# design.net
KiCad netlist of a schematic drawn in EasyEDA Pro
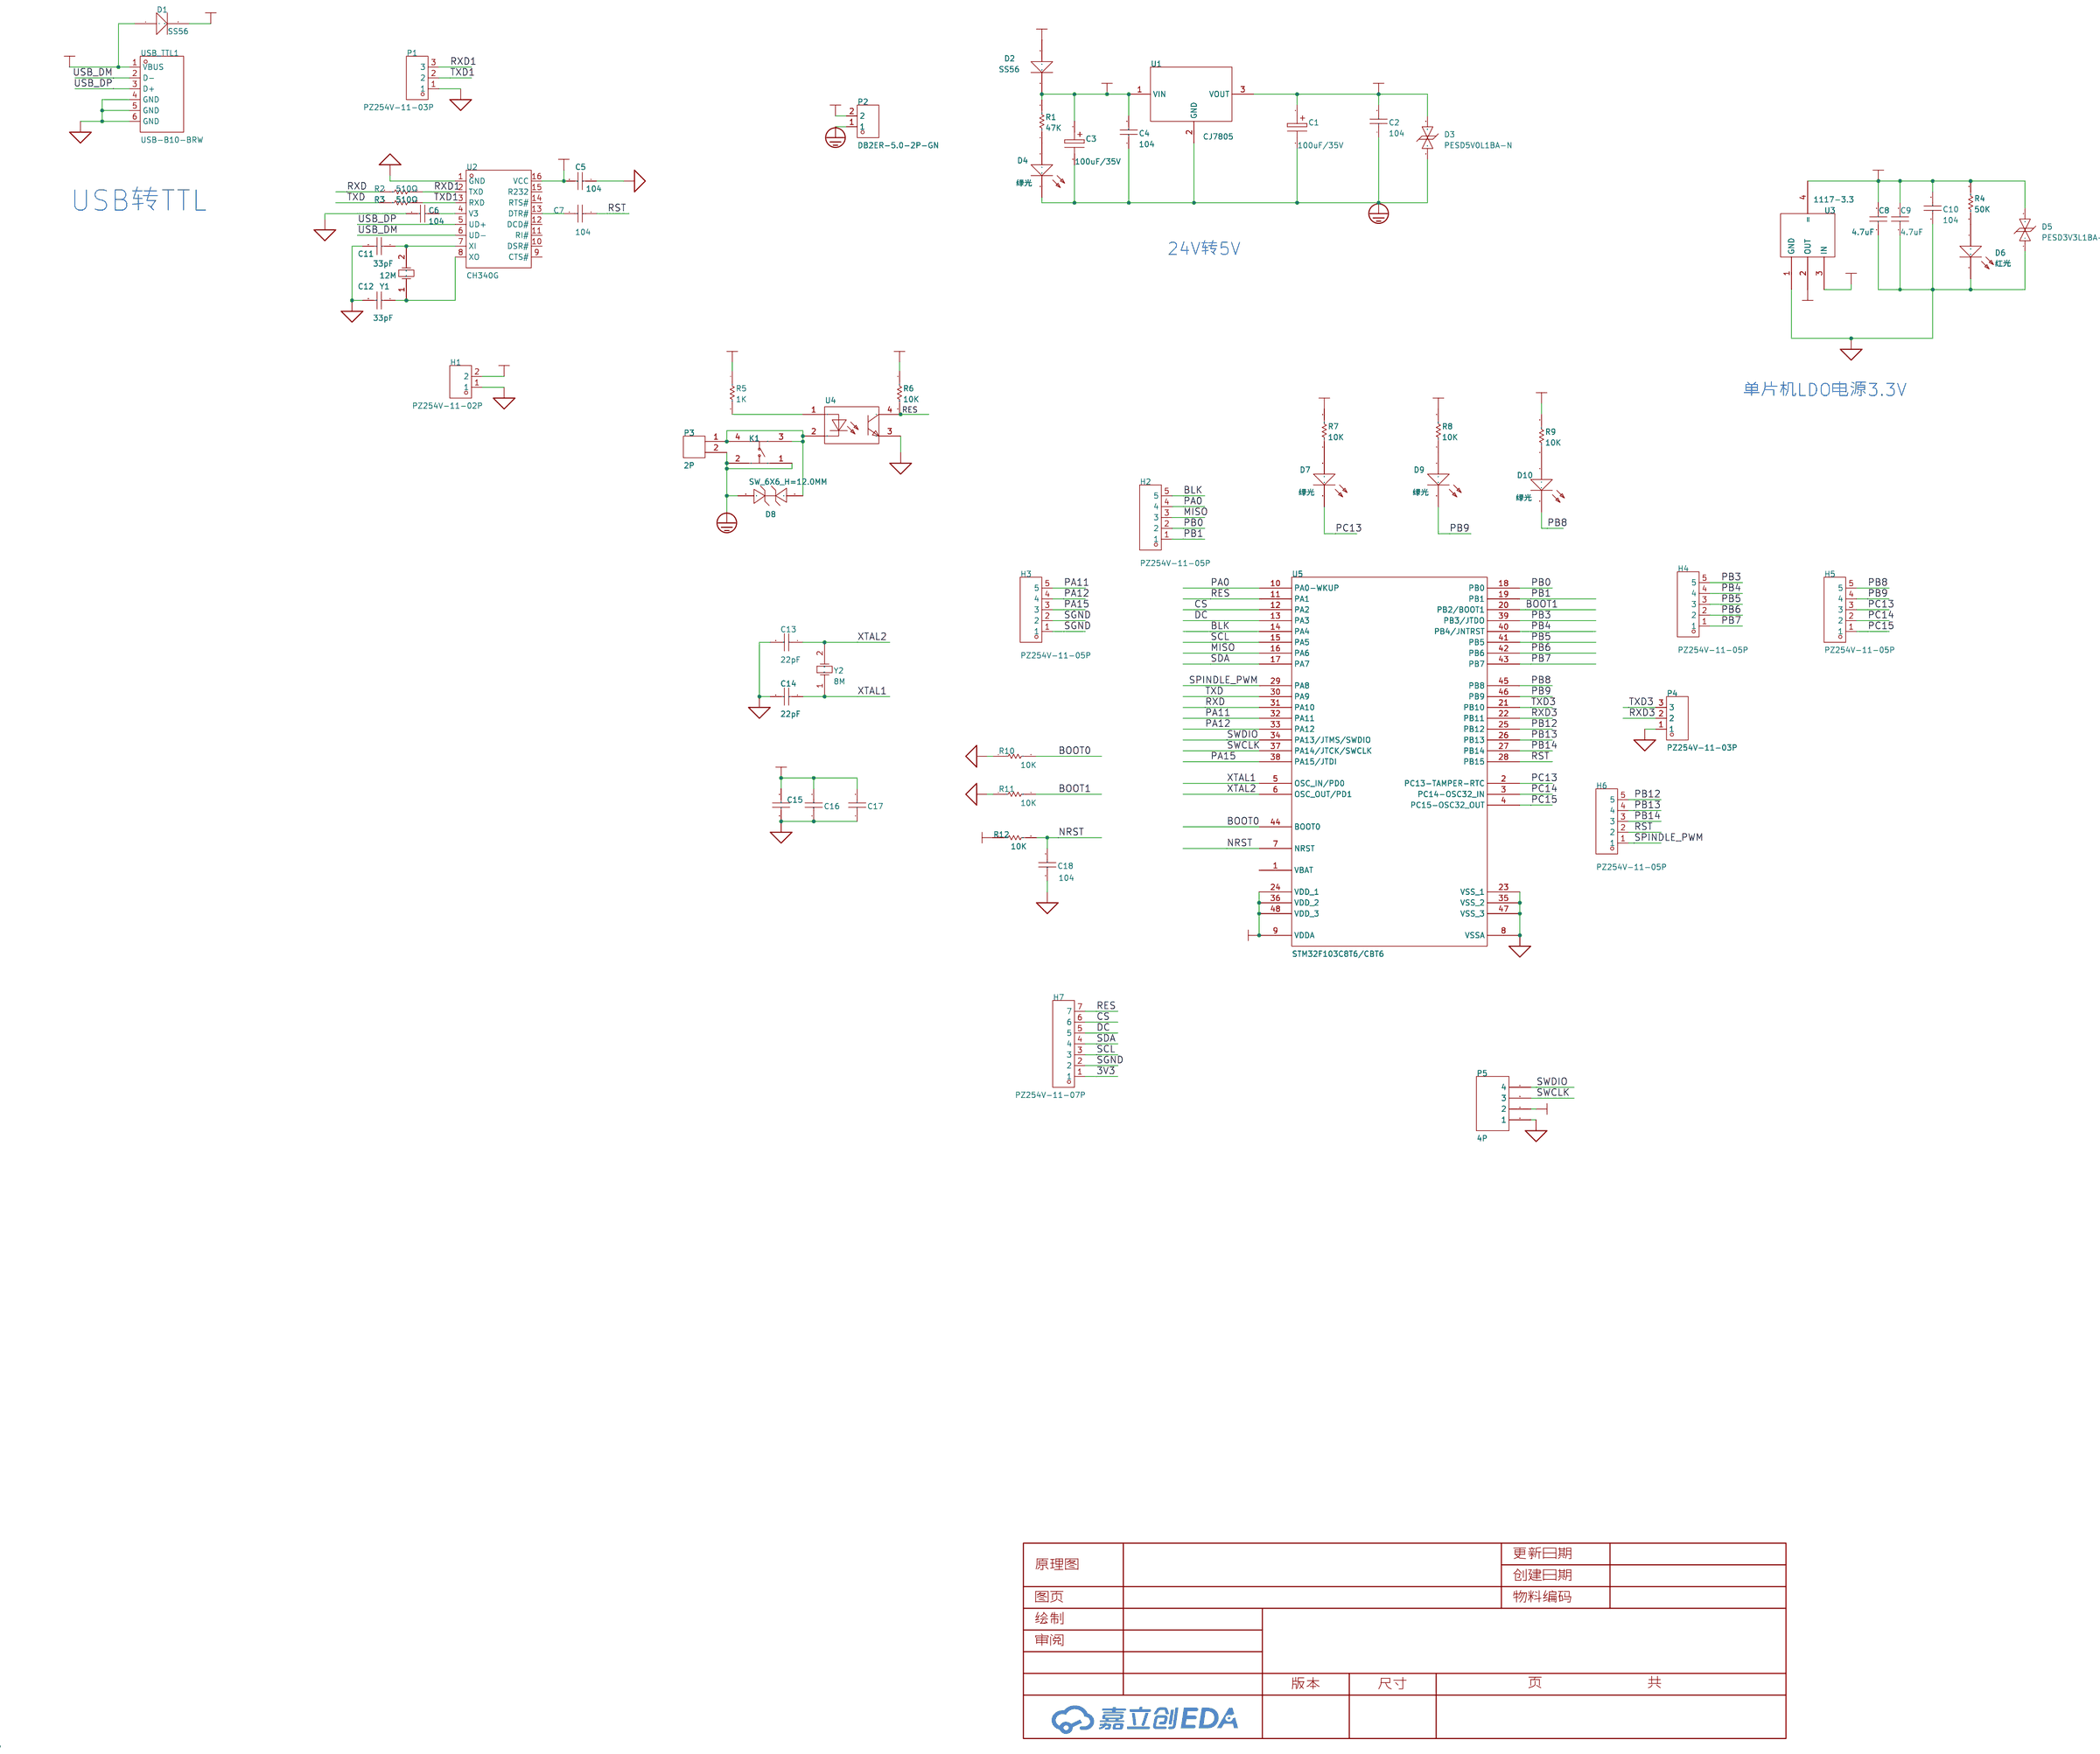
[diagram p0: 主控MCU]
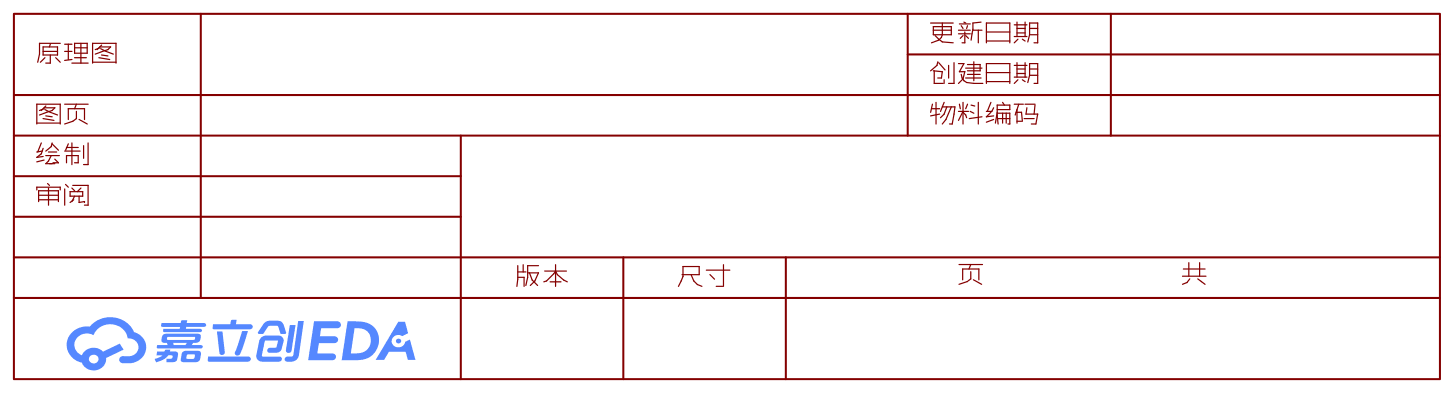
[diagram p1: 电源及控制]

(export (version "E")
  (design (tool "Eeschema 10.0.6"))
  (components
    (comp (ref "C1")
      (value "100uF/35V")
      (footprint "easyedapro:0603C")
      (libsource (lib "easyedapro") (part "ELECTRO1"))
    )
    (comp (ref "C2")
      (value "104")
      (footprint "easyedapro:0603C")
      (description "Capacitor (Semiconductor SIM Model)")
      (libsource (lib "easyedapro") (part "Cap Semi"))
    )
    (comp (ref "C3")
      (value "100uF/35V")
      (footprint "easyedapro:0603C")
      (libsource (lib "easyedapro") (part "ELECTRO1"))
    )
    (comp (ref "C4")
      (value "104")
      (footprint "easyedapro:0603C")
      (description "Capacitor (Semiconductor SIM Model)")
      (libsource (lib "easyedapro") (part "Cap Semi"))
    )
    (comp (ref "C5")
      (value "104")
      (footprint "easyedapro:0603C")
      (description "Capacitor (Semiconductor SIM Model)")
      (libsource (lib "easyedapro") (part "Cap Semi"))
    )
    (comp (ref "C6")
      (value "104")
      (footprint "easyedapro:0603C")
      (description "Capacitor (Semiconductor SIM Model)")
      (libsource (lib "easyedapro") (part "Cap Semi"))
    )
    (comp (ref "C7")
      (value "104")
      (footprint "easyedapro:0603C")
      (description "Capacitor (Semiconductor SIM Model)")
      (libsource (lib "easyedapro") (part "Cap Semi"))
    )
    (comp (ref "C8") (value "4.7uF") (libsource (lib "") (part "CAP_1")))
    (comp (ref "C9") (value "4.7uF") (libsource (lib "") (part "CAP_1")))
    (comp (ref "C10")
      (value "104")
      (footprint "easyedapro:0603C")
      (description "Capacitor (Semiconductor SIM Model)")
      (libsource (lib "easyedapro") (part "Cap Semi"))
    )
    (comp (ref "C11")
      (value "18pF")
      (footprint "easyedapro:0603C")
      (description "Capacitor (Semiconductor SIM Model)")
      (libsource (lib "easyedapro") (part "Cap Semi"))
    )
    (comp (ref "C12")
      (value "18pF")
      (footprint "easyedapro:0603C")
      (description "Capacitor (Semiconductor SIM Model)")
      (libsource (lib "easyedapro") (part "Cap Semi"))
    )
    (comp (ref "C13")
      (value "100pF")
      (footprint "easyedapro:0603C")
      (description "Capacitor (Semiconductor SIM Model)")
      (libsource (lib "easyedapro") (part "Cap Semi"))
    )
    (comp (ref "C14")
      (value "100pF")
      (footprint "easyedapro:0603C")
      (description "Capacitor (Semiconductor SIM Model)")
      (libsource (lib "easyedapro") (part "Cap Semi"))
    )
    (comp (ref "C15")
      (value "104")
      (footprint "easyedapro:电解电容贴片6X6")
      (libsource (lib "easyedapro") (part "CAP"))
    )
    (comp (ref "C16")
      (value "104")
      (footprint "easyedapro:电解电容贴片6X6")
      (libsource (lib "easyedapro") (part "CAP"))
    )
    (comp (ref "C17")
      (value "104")
      (footprint "easyedapro:电解电容贴片6X6")
      (libsource (lib "easyedapro") (part "CAP"))
    )
    (comp (ref "C18")
      (value "104")
      (footprint "easyedapro:0603C")
      (description "Capacitor (Semiconductor SIM Model)")
      (libsource (lib "easyedapro") (part "Cap Semi"))
    )
    (comp (ref "D1")
      (value "SS56")
      (footprint "easyedapro:SMA")
      (libsource (lib "easyedapro") (part "1N4148"))
    )
    (comp (ref "D2")
      (value "SS56")
      (footprint "easyedapro:SMA")
      (libsource (lib "easyedapro") (part "1N4148"))
    )
    (comp (ref "D3")
      (value "PESD5V0L1BA-N")
      (footprint "easyedapro:SOD-523_L1.2-W0.8-LS1.6-BI")
      (description "极性:Bidirectional;反向关断电压（典型值）:5V (Max);击穿电压（最小值）:6V;箝位电压:15V;峰值脉冲电流（10/1000us）:5A (8/20us);")
      (fields (field (name "Manufacturer") "BORN伯恩半导体"))
      (libsource (lib "easyedapro") (part "PESD5V0S1BBN"))
    )
    (comp (ref "D4")
      (value "绿光")
      (footprint "easyedapro:0603LED")
      (libsource (lib "easyedapro") (part "LED"))
    )
    (comp (ref "D5")
      (value "PESD3V3L1BA-N")
      (footprint "easyedapro:SOD-523_L1.2-W0.8-LS1.6-BI")
      (description "极性:Bidirectional;反向关断电压（典型值）:5V (Max);击穿电压（最小值）:6V;箝位电压:15V;峰值脉冲电流（10/1000us）:5A (8/20us);")
      (fields (field (name "Manufacturer") "BORN伯恩半导体"))
      (libsource (lib "easyedapro") (part "PESD5V0S1BBN"))
    )
    (comp (ref "D6")
      (value "红光")
      (footprint "easyedapro:0603LED")
      (libsource (lib "easyedapro") (part "LED"))
    )
    (comp (ref "D7")
      (value "绿光")
      (footprint "easyedapro:0603LED")
      (libsource (lib "easyedapro") (part "LED"))
    )
    (comp (ref "D8")
      (value "ESD05V52D-C")
      (footprint "easyedapro:SOD-523_L1.2-W0.8-LS1.6-BI")
      (fields (field (name "Manufacturer") "TWGMC(台湾迪嘉)"))
      (libsource (lib "easyedapro") (part "ESD05V52D-C"))
    )
    (comp (ref "D9")
      (value "绿光")
      (footprint "easyedapro:0603LED")
      (libsource (lib "easyedapro") (part "LED"))
    )
    (comp (ref "D10")
      (value "绿光")
      (footprint "easyedapro:0603LED")
      (libsource (lib "easyedapro") (part "LED"))
    )
    (comp (ref "H1")
      (value "PZ254V-11-02P")
      (footprint "easyedapro:HDR-TH_2P-P2.54-V-M")
      (fields (field (name "Manufacturer") "XFCN(兴飞)"))
      (libsource (lib "easyedapro") (part "PZ254V-11-02P"))
    )
    (comp (ref "H2")
      (value "PZ254V-11-05P")
      (footprint "easyedapro:HDR-TH_5P-P2.54-V-M")
      (fields (field (name "Manufacturer") "XFCN(兴飞)"))
      (libsource (lib "easyedapro") (part "PZ254V-11-05P"))
    )
    (comp (ref "H3")
      (value "PZ254V-11-05P")
      (footprint "easyedapro:HDR-TH_5P-P2.54-V-M")
      (fields (field (name "Manufacturer") "XFCN(兴飞)"))
      (libsource (lib "easyedapro") (part "PZ254V-11-05P"))
    )
    (comp (ref "H4")
      (value "PZ254V-11-05P")
      (footprint "easyedapro:HDR-TH_5P-P2.54-V-M")
      (fields (field (name "Manufacturer") "XFCN(兴飞)"))
      (libsource (lib "easyedapro") (part "PZ254V-11-05P"))
    )
    (comp (ref "H5")
      (value "PZ254V-11-05P")
      (footprint "easyedapro:HDR-TH_5P-P2.54-V-M")
      (fields (field (name "Manufacturer") "XFCN(兴飞)"))
      (libsource (lib "easyedapro") (part "PZ254V-11-05P"))
    )
    (comp (ref "H6")
      (value "PZ254V-11-05P")
      (footprint "easyedapro:HDR-TH_5P-P2.54-V-M")
      (fields (field (name "Manufacturer") "XFCN(兴飞)"))
      (libsource (lib "easyedapro") (part "PZ254V-11-05P"))
    )
    (comp (ref "H7")
      (value "PZ254V-11-07P")
      (footprint "easyedapro:HDR-TH_7P-P2.54-V-M")
      (fields (field (name "Manufacturer") "XFCN(兴飞)"))
      (libsource (lib "easyedapro") (part "PZ254V-11-07P"))
    )
    (comp (ref "K1")
      (value "SW_6X6_H=12.0MM")
      (footprint "easyedapro:KEY-SMD_4P-L6.0-W6.0-P4.50-LS9.0")
      (libsource (lib "easyedapro") (part "SW_6X6_H=12.0MM"))
    )
    (comp (ref "P1")
      (value "PZ254V-11-03P")
      (footprint "easyedapro:HDR-TH_3P-P2.54-V-M")
      (fields (field (name "Manufacturer") "XFCN(兴飞)"))
      (libsource (lib "easyedapro") (part "PZ254V-11-03P_C2937625"))
    )
    (comp (ref "P2")
      (value "DB2ER-5.0-2P-GN")
      (footprint "easyedapro:CONN-TH_2P-P5.00_DB2ER-5.0-2P-GN")
      (description "间距:5mm;颜色:绿色;排数:1;每排PIN数:2;额定电流:15A;额定电压:630V;触头镀层:锡;")
      (fields (field (name "Manufacturer") "DORABO(地博电气)"))
      (libsource (lib "easyedapro") (part "DB2ER-5.0-2P-GN"))
    )
    (comp (ref "P3") (value "2P") (libsource (lib "easyedapro") (part "2P")))
    (comp (ref "P4")
      (value "PZ254V-11-03P")
      (footprint "easyedapro:HDR-TH_3P-P2.54-V-M")
      (fields (field (name "Manufacturer") "XFCN(兴飞)"))
      (libsource (lib "easyedapro") (part "PZ254V-11-03P_C2937625"))
    )
    (comp (ref "P5") (value "4P") (libsource (lib "easyedapro") (part "4P")))
    (comp (ref "R1")
      (value "47K")
      (footprint "easyedapro:0603R")
      (description "Resistor")
      (libsource (lib "easyedapro") (part "RES"))
    )
    (comp (ref "R2")
      (value "510Ω")
      (footprint "easyedapro:0603R")
      (description "Resistor")
      (libsource (lib "easyedapro") (part "RES"))
    )
    (comp (ref "R3")
      (value "510Ω")
      (footprint "easyedapro:0603R")
      (description "Resistor")
      (libsource (lib "easyedapro") (part "RES"))
    )
    (comp (ref "R4")
      (value "50K")
      (footprint "easyedapro:0603R")
      (description "Resistor")
      (libsource (lib "easyedapro") (part "RES"))
    )
    (comp (ref "R5")
      (value "1K")
      (footprint "easyedapro:0603R")
      (description "Resistor")
      (libsource (lib "easyedapro") (part "RES"))
    )
    (comp (ref "R6")
      (value "10K")
      (footprint "easyedapro:0603R")
      (description "Resistor")
      (libsource (lib "easyedapro") (part "RES"))
    )
    (comp (ref "R7")
      (value "10K")
      (footprint "easyedapro:0603R")
      (description "Resistor")
      (libsource (lib "easyedapro") (part "RES"))
    )
    (comp (ref "R8")
      (value "10K")
      (footprint "easyedapro:0603R")
      (description "Resistor")
      (libsource (lib "easyedapro") (part "RES"))
    )
    (comp (ref "R9")
      (value "10K")
      (footprint "easyedapro:0603R")
      (description "Resistor")
      (libsource (lib "easyedapro") (part "RES"))
    )
    (comp (ref "R10")
      (value "10K")
      (footprint "easyedapro:0603R")
      (description "Resistor")
      (libsource (lib "easyedapro") (part "RES"))
    )
    (comp (ref "R11")
      (value "10K")
      (footprint "easyedapro:0603R")
      (description "Resistor")
      (libsource (lib "easyedapro") (part "RES"))
    )
    (comp (ref "R12")
      (value "10K")
      (footprint "easyedapro:0603R")
      (description "Resistor")
      (libsource (lib "easyedapro") (part "RES"))
    )
    (comp (ref "U1")
      (value "CJ7805")
      (footprint "easyedapro:TO-263-2")
      (libsource (lib "easyedapro") (part "7805"))
    )
    (comp (ref "U2")
      (value "CH340G")
      (footprint "easyedapro:SOIC-16_L9.9-W3.9-P1.27-LS6.0-BL")
      (description "应用功能:收发器;接口协议:USB 2.0;数据速率:2Mbps;")
      (fields (field (name "Manufacturer") "WCH(南京沁恒)"))
      (libsource (lib "easyedapro") (part "CH340G"))
    )
    (comp (ref "U3")
      (value "1117-3.3")
      (footprint "easyedapro:SOT-223")
      (libsource (lib "easyedapro") (part "LM1117"))
    )
    (comp (ref "U4")
      (value "LTV-357T-C")
      (footprint "easyedapro:SOP-4_L4.4-W3.9-P2.54-LS7.0-TL")
      (fields (field (name "Manufacturer") "LITEON(光宝)"))
      (libsource (lib "easyedapro") (part "LTV-357T-C"))
    )
    (comp (ref "U5")
      (value "STM32F103C8T6/CBT6")
      (footprint "easyedapro:LQFP48")
      (description "STM32 ARM-based 32-bit MCU with 32 Kbytes Flash, 48-pin LQFP, Industrial Temperature")
      (libsource (lib "easyedapro") (part "STM32F103C6T6"))
    )
    (comp (ref "USB_TTL1")
      (value "USB-B10-BRW")
      (footprint "easyedapro:USB-B-TH_USB-B10-BRW")
      (fields (field (name "Manufacturer") "XUNPU(讯普)"))
      (libsource (lib "easyedapro") (part "USB-B10-BRW"))
    )
    (comp (ref "Y1")
      (value "12M")
      (footprint "easyedapro:晶振贴片49SSMD")
      (description "Crystal Oscillator")
      (libsource (lib "easyedapro") (part "XTAL"))
    )
    (comp (ref "Y2")
      (value "8M")
      (footprint "easyedapro:晶振贴片49SSMD")
      (description "Crystal Oscillator")
      (libsource (lib "easyedapro") (part "XTAL"))
    )
  )
  (nets
    (net (code "1") (name "3V3") (class "Default")
      (node (ref "C10") (pin "2") (pinfunction "2_2") (pintype "unspecified"))
      (node (ref "C15") (pin "2") (pinfunction "2_2") (pintype "unspecified"))
      (node (ref "C16") (pin "2") (pinfunction "2_2") (pintype "unspecified"))
      (node (ref "C17") (pin "2") (pinfunction "2_2") (pintype "unspecified"))
      (node (ref "C8") (pin "2") (pinfunction "2_2") (pintype "input"))
      (node (ref "C9") (pin "2") (pinfunction "2_2") (pintype "input"))
      (node (ref "D5") (pin "2") (pinfunction "2_2") (pintype "input"))
      (node (ref "H7") (pin "1") (pinfunction "1_1") (pintype "unspecified"))
      (node (ref "P5") (pin "2") (pinfunction "2_2") (pintype "input"))
      (node (ref "R12") (pin "1") (pinfunction "1_1") (pintype "unspecified"))
      (node (ref "R4") (pin "1") (pinfunction "1_1") (pintype "unspecified"))
      (node (ref "R6") (pin "1") (pinfunction "1_1") (pintype "unspecified"))
      (node (ref "R7") (pin "2") (pinfunction "2_2") (pintype "unspecified"))
      (node (ref "R8") (pin "2") (pinfunction "2_2") (pintype "unspecified"))
      (node (ref "R9") (pin "2") (pinfunction "2_2") (pintype "unspecified"))
      (node (ref "U3") (pin "2") (pinfunction "OUT_2") (pintype "unspecified"))
      (node (ref "U3") (pin "4") (pinfunction "=_4") (pintype "unspecified"))
      (node (ref "U5") (pin "24") (pinfunction "VDD_1_24") (pintype "unspecified"))
      (node (ref "U5") (pin "36") (pinfunction "VDD_2_36") (pintype "unspecified"))
      (node (ref "U5") (pin "48") (pinfunction "VDD_3_48") (pintype "unspecified"))
      (node (ref "U5") (pin "9") (pinfunction "VDDA_9") (pintype "unspecified"))
    )
    (net (code "2") (name "5V_VCC") (class "Default")
      (node (ref "C1") (pin "1") (pintype "unspecified"))
      (node (ref "C2") (pin "2") (pinfunction "2_2") (pintype "unspecified"))
      (node (ref "C5") (pin "2") (pinfunction "2_2") (pintype "unspecified"))
      (node (ref "D1") (pin "2") (pinfunction "2_2") (pintype "unspecified"))
      (node (ref "D3") (pin "2") (pinfunction "2_2") (pintype "input"))
      (node (ref "H1") (pin "2") (pinfunction "2_2") (pintype "unspecified"))
      (node (ref "R5") (pin "1") (pinfunction "1_1") (pintype "unspecified"))
      (node (ref "U1") (pin "3") (pinfunction "VOUT_3") (pintype "unspecified"))
      (node (ref "U2") (pin "16") (pinfunction "VCC_16") (pintype "unspecified"))
      (node (ref "U3") (pin "3") (pinfunction "IN_3") (pintype "unspecified"))
    )
    (net (code "3") (name "24V") (class "Default")
      (node (ref "D2") (pin "1") (pinfunction "1_1") (pintype "unspecified"))
      (node (ref "P2") (pin "2") (pinfunction "2_2") (pintype "unspecified"))
    )
    (net (code "4") (name "BLK") (class "Default")
      (node (ref "H2") (pin "5") (pinfunction "5_5") (pintype "input"))
      (node (ref "U5") (pin "14") (pinfunction "PA4_14") (pintype "bidirectional"))
    )
    (net (code "5") (name "BOOT0") (class "Default")
      (node (ref "R10") (pin "2") (pinfunction "2_2") (pintype "unspecified"))
      (node (ref "U5") (pin "44") (pinfunction "BOOT0_44") (pintype "input"))
    )
    (net (code "6") (name "BOOT1") (class "Default")
      (node (ref "R11") (pin "2") (pinfunction "2_2") (pintype "unspecified"))
      (node (ref "U5") (pin "20") (pinfunction "PB2/BOOT1_20") (pintype "bidirectional"))
    )
    (net (code "7") (name "CS") (class "Default")
      (node (ref "H7") (pin "6") (pinfunction "6_6") (pintype "unspecified"))
      (node (ref "U5") (pin "12") (pinfunction "PA2_12") (pintype "bidirectional"))
    )
    (net (code "8") (name "DC") (class "Default")
      (node (ref "H7") (pin "5") (pinfunction "5_5") (pintype "unspecified"))
      (node (ref "U5") (pin "13") (pinfunction "PA3_13") (pintype "bidirectional"))
    )
    (net (code "9") (name "MISO") (class "Default")
      (node (ref "H2") (pin "3") (pinfunction "3_3") (pintype "input"))
      (node (ref "U5") (pin "16") (pinfunction "PA6_16") (pintype "bidirectional"))
    )
    (net (code "10") (name "NRST") (class "Default")
      (node (ref "C18") (pin "2") (pinfunction "2_2") (pintype "unspecified"))
      (node (ref "R12") (pin "2") (pinfunction "2_2") (pintype "unspecified"))
      (node (ref "U5") (pin "7") (pinfunction "NRST_7") (pintype "bidirectional"))
    )
    (net (code "11") (name "Net-(D4-Pad1)") (class "Default")
      (node (ref "D4") (pin "1") (pinfunction "1_1") (pintype "unspecified"))
      (node (ref "R1") (pin "1") (pinfunction "1_1") (pintype "unspecified"))
    )
    (net (code "12") (name "Net-(D6-Pad1)") (class "Default")
      (node (ref "D6") (pin "1") (pinfunction "1_1") (pintype "unspecified"))
      (node (ref "R4") (pin "2") (pinfunction "2_2") (pintype "unspecified"))
    )
    (net (code "13") (name "Net-(D7-Pad1)") (class "Default")
      (node (ref "D7") (pin "1") (pinfunction "1_1") (pintype "unspecified"))
      (node (ref "R7") (pin "1") (pinfunction "1_1") (pintype "unspecified"))
    )
    (net (code "14") (name "Net-(D8-Pad2)") (class "Default")
      (node (ref "D8") (pin "2") (pinfunction "2_2") (pintype "unspecified"))
      (node (ref "K1") (pin "3") (pinfunction "3_3") (pintype "unspecified"))
      (node (ref "K1") (pin "4") (pinfunction "4_4") (pintype "unspecified"))
      (node (ref "P3") (pin "1") (pintype "input"))
      (node (ref "U4") (pin "2") (pinfunction "2_2") (pintype "unspecified"))
    )
    (net (code "15") (name "Net-(D9-Pad1)") (class "Default")
      (node (ref "D9") (pin "1") (pinfunction "1_1") (pintype "unspecified"))
      (node (ref "R8") (pin "1") (pinfunction "1_1") (pintype "unspecified"))
    )
    (net (code "16") (name "Net-(D10-Pad1)") (class "Default")
      (node (ref "D10") (pin "1") (pinfunction "1_1") (pintype "unspecified"))
      (node (ref "R9") (pin "1") (pinfunction "1_1") (pintype "unspecified"))
    )
    (net (code "17") (name "Net-(R5-Pad2)") (class "Default")
      (node (ref "R5") (pin "2") (pinfunction "2_2") (pintype "unspecified"))
      (node (ref "U4") (pin "1") (pinfunction "1_1") (pintype "unspecified"))
    )
    (net (code "18") (name "Net-(U2-DTR#)") (class "Default")
      (node (ref "C7") (pin "1") (pinfunction "1_1") (pintype "unspecified"))
      (node (ref "U2") (pin "13") (pinfunction "DTR#_13") (pintype "unspecified"))
    )
    (net (code "19") (name "Net-(U2-V3)") (class "Default")
      (node (ref "C6") (pin "1") (pinfunction "1_1") (pintype "unspecified"))
      (node (ref "U2") (pin "4") (pinfunction "V3_4") (pintype "unspecified"))
    )
    (net (code "20") (name "Net-(U2-XI)") (class "Default")
      (node (ref "C11") (pin "1") (pinfunction "1_1") (pintype "unspecified"))
      (node (ref "U2") (pin "7") (pinfunction "XI_7") (pintype "unspecified"))
      (node (ref "Y1") (pin "2") (pinfunction "OSC2_2") (pintype "unspecified"))
    )
    (net (code "21") (name "Net-(U2-XO)") (class "Default")
      (node (ref "C12") (pin "1") (pinfunction "1_1") (pintype "unspecified"))
      (node (ref "U2") (pin "8") (pinfunction "XO_8") (pintype "unspecified"))
      (node (ref "Y1") (pin "1") (pinfunction "OSC1_1") (pintype "unspecified"))
    )
    (net (code "22") (name "PA0") (class "Default")
      (node (ref "H2") (pin "4") (pinfunction "4_4") (pintype "input"))
      (node (ref "U5") (pin "10") (pinfunction "PA0-WKUP_10") (pintype "bidirectional"))
    )
    (net (code "23") (name "PA11") (class "Default")
      (node (ref "H3") (pin "5") (pinfunction "5_5") (pintype "input"))
      (node (ref "U5") (pin "32") (pinfunction "PA11_32") (pintype "bidirectional"))
    )
    (net (code "24") (name "PA12") (class "Default")
      (node (ref "H3") (pin "4") (pinfunction "4_4") (pintype "input"))
      (node (ref "U5") (pin "33") (pinfunction "PA12_33") (pintype "bidirectional"))
    )
    (net (code "25") (name "PA15") (class "Default")
      (node (ref "H3") (pin "3") (pinfunction "3_3") (pintype "input"))
      (node (ref "U5") (pin "38") (pinfunction "PA15/JTDI_38") (pintype "bidirectional"))
    )
    (net (code "26") (name "PB0") (class "Default")
      (node (ref "H2") (pin "2") (pinfunction "2_2") (pintype "input"))
      (node (ref "U5") (pin "18") (pinfunction "PB0_18") (pintype "bidirectional"))
    )
    (net (code "27") (name "PB1") (class "Default")
      (node (ref "H2") (pin "1") (pinfunction "1_1") (pintype "input"))
      (node (ref "U5") (pin "19") (pinfunction "PB1_19") (pintype "bidirectional"))
    )
    (net (code "28") (name "PB3") (class "Default")
      (node (ref "H4") (pin "5") (pinfunction "5_5") (pintype "input"))
      (node (ref "U5") (pin "39") (pinfunction "PB3/JTDO_39") (pintype "bidirectional"))
    )
    (net (code "29") (name "PB4") (class "Default")
      (node (ref "H4") (pin "4") (pinfunction "4_4") (pintype "input"))
      (node (ref "U5") (pin "40") (pinfunction "PB4/JNTRST_40") (pintype "bidirectional"))
    )
    (net (code "30") (name "PB5") (class "Default")
      (node (ref "H4") (pin "3") (pinfunction "3_3") (pintype "input"))
      (node (ref "U5") (pin "41") (pinfunction "PB5_41") (pintype "bidirectional"))
    )
    (net (code "31") (name "PB6") (class "Default")
      (node (ref "H4") (pin "2") (pinfunction "2_2") (pintype "input"))
      (node (ref "U5") (pin "42") (pinfunction "PB6_42") (pintype "bidirectional"))
    )
    (net (code "32") (name "PB7") (class "Default")
      (node (ref "H4") (pin "1") (pinfunction "1_1") (pintype "input"))
      (node (ref "U5") (pin "43") (pinfunction "PB7_43") (pintype "bidirectional"))
    )
    (net (code "33") (name "PB8") (class "Default")
      (node (ref "D10") (pin "2") (pinfunction "2_2") (pintype "unspecified"))
      (node (ref "H5") (pin "5") (pinfunction "5_5") (pintype "input"))
      (node (ref "U5") (pin "45") (pinfunction "PB8_45") (pintype "bidirectional"))
    )
    (net (code "34") (name "PB9") (class "Default")
      (node (ref "D9") (pin "2") (pinfunction "2_2") (pintype "unspecified"))
      (node (ref "H5") (pin "4") (pinfunction "4_4") (pintype "input"))
      (node (ref "U5") (pin "46") (pinfunction "PB9_46") (pintype "bidirectional"))
    )
    (net (code "35") (name "PB12") (class "Default")
      (node (ref "H6") (pin "5") (pinfunction "5_5") (pintype "input"))
      (node (ref "U5") (pin "25") (pinfunction "PB12_25") (pintype "bidirectional"))
    )
    (net (code "36") (name "PB13") (class "Default")
      (node (ref "H6") (pin "4") (pinfunction "4_4") (pintype "input"))
      (node (ref "U5") (pin "26") (pinfunction "PB13_26") (pintype "bidirectional"))
    )
    (net (code "37") (name "PB14") (class "Default")
      (node (ref "H6") (pin "3") (pinfunction "3_3") (pintype "input"))
      (node (ref "U5") (pin "27") (pinfunction "PB14_27") (pintype "bidirectional"))
    )
    (net (code "38") (name "PC13") (class "Default")
      (node (ref "D7") (pin "2") (pinfunction "2_2") (pintype "unspecified"))
      (node (ref "H5") (pin "3") (pinfunction "3_3") (pintype "input"))
      (node (ref "U5") (pin "2") (pinfunction "PC13-TAMPER-RTC_2") (pintype "bidirectional"))
    )
    (net (code "39") (name "PC14") (class "Default")
      (node (ref "H5") (pin "2") (pinfunction "2_2") (pintype "input"))
      (node (ref "U5") (pin "3") (pinfunction "PC14-OSC32_IN_3") (pintype "bidirectional"))
    )
    (net (code "40") (name "PC15") (class "Default")
      (node (ref "H5") (pin "1") (pinfunction "1_1") (pintype "input"))
      (node (ref "U5") (pin "4") (pinfunction "PC15-OSC32_OUT_4") (pintype "bidirectional"))
    )
    (net (code "41") (name "RES") (class "Default")
      (node (ref "H7") (pin "7") (pinfunction "7_7") (pintype "unspecified"))
      (node (ref "R6") (pin "2") (pinfunction "2_2") (pintype "unspecified"))
      (node (ref "U4") (pin "4") (pinfunction "4_4") (pintype "unspecified"))
      (node (ref "U5") (pin "11") (pinfunction "PA1_11") (pintype "bidirectional"))
    )
    (net (code "42") (name "RST") (class "Default")
      (node (ref "C7") (pin "2") (pinfunction "2_2") (pintype "unspecified"))
      (node (ref "H6") (pin "2") (pinfunction "2_2") (pintype "input"))
      (node (ref "U5") (pin "28") (pinfunction "PB15_28") (pintype "bidirectional"))
    )
    (net (code "43") (name "RXD") (class "Default")
      (node (ref "R2") (pin "2") (pinfunction "2_2") (pintype "unspecified"))
      (node (ref "U5") (pin "31") (pinfunction "PA10_31") (pintype "bidirectional"))
    )
    (net (code "44") (name "RXD1") (class "Default")
      (node (ref "P1") (pin "3") (pinfunction "3_3") (pintype "unspecified"))
      (node (ref "R2") (pin "1") (pinfunction "1_1") (pintype "unspecified"))
      (node (ref "U2") (pin "2") (pinfunction "TXD_2") (pintype "unspecified"))
    )
    (net (code "45") (name "RXD3") (class "Default")
      (node (ref "P4") (pin "2") (pinfunction "2_2") (pintype "unspecified"))
      (node (ref "U5") (pin "22") (pinfunction "PB11_22") (pintype "bidirectional"))
    )
    (net (code "46") (name "SCL") (class "Default")
      (node (ref "H7") (pin "3") (pinfunction "3_3") (pintype "unspecified"))
      (node (ref "U5") (pin "15") (pinfunction "PA5_15") (pintype "bidirectional"))
    )
    (net (code "47") (name "SDA") (class "Default")
      (node (ref "H7") (pin "4") (pinfunction "4_4") (pintype "unspecified"))
      (node (ref "U5") (pin "17") (pinfunction "PA7_17") (pintype "bidirectional"))
    )
    (net (code "48") (name "SGND") (class "Default")
      (node (ref "C1") (pin "2") (pintype "unspecified"))
      (node (ref "C10") (pin "1") (pinfunction "1_1") (pintype "unspecified"))
      (node (ref "C11") (pin "2") (pinfunction "2_2") (pintype "unspecified"))
      (node (ref "C12") (pin "2") (pinfunction "2_2") (pintype "unspecified"))
      (node (ref "C13") (pin "2") (pinfunction "2_2") (pintype "unspecified"))
      (node (ref "C14") (pin "2") (pinfunction "2_2") (pintype "unspecified"))
      (node (ref "C15") (pin "1") (pinfunction "1_1") (pintype "unspecified"))
      (node (ref "C16") (pin "1") (pinfunction "1_1") (pintype "unspecified"))
      (node (ref "C17") (pin "1") (pinfunction "1_1") (pintype "unspecified"))
      (node (ref "C18") (pin "1") (pinfunction "1_1") (pintype "unspecified"))
      (node (ref "C2") (pin "1") (pinfunction "1_1") (pintype "unspecified"))
      (node (ref "C3") (pin "2") (pintype "unspecified"))
      (node (ref "C4") (pin "1") (pinfunction "1_1") (pintype "unspecified"))
      (node (ref "C5") (pin "1") (pinfunction "1_1") (pintype "unspecified"))
      (node (ref "C6") (pin "2") (pinfunction "2_2") (pintype "unspecified"))
      (node (ref "C8") (pin "1") (pinfunction "1_1") (pintype "input"))
      (node (ref "C9") (pin "1") (pinfunction "1_1") (pintype "input"))
      (node (ref "D3") (pin "1") (pinfunction "1_1") (pintype "input"))
      (node (ref "D4") (pin "2") (pinfunction "2_2") (pintype "unspecified"))
      (node (ref "D5") (pin "1") (pinfunction "1_1") (pintype "input"))
      (node (ref "D6") (pin "2") (pinfunction "2_2") (pintype "unspecified"))
      (node (ref "D8") (pin "1") (pinfunction "1_1") (pintype "unspecified"))
      (node (ref "H1") (pin "1") (pinfunction "1_1") (pintype "unspecified"))
      (node (ref "H3") (pin "1") (pinfunction "1_1") (pintype "input"))
      (node (ref "H3") (pin "2") (pinfunction "2_2") (pintype "input"))
      (node (ref "H7") (pin "2") (pinfunction "2_2") (pintype "unspecified"))
      (node (ref "K1") (pin "1") (pinfunction "1_1") (pintype "unspecified"))
      (node (ref "K1") (pin "2") (pinfunction "2_2") (pintype "unspecified"))
      (node (ref "P1") (pin "1") (pinfunction "1_1") (pintype "unspecified"))
      (node (ref "P2") (pin "1") (pinfunction "1_1") (pintype "unspecified"))
      (node (ref "P3") (pin "2") (pintype "input"))
      (node (ref "P4") (pin "1") (pinfunction "1_1") (pintype "unspecified"))
      (node (ref "P5") (pin "1") (pinfunction "1_1") (pintype "input"))
      (node (ref "R10") (pin "1") (pinfunction "1_1") (pintype "unspecified"))
      (node (ref "R11") (pin "1") (pinfunction "1_1") (pintype "unspecified"))
      (node (ref "U1") (pin "2") (pinfunction "GND_2") (pintype "unspecified"))
      (node (ref "U2") (pin "1") (pinfunction "GND_1") (pintype "unspecified"))
      (node (ref "U3") (pin "1") (pinfunction "GND_1") (pintype "unspecified"))
      (node (ref "U4") (pin "3") (pinfunction "3_3") (pintype "unspecified"))
      (node (ref "U5") (pin "23") (pinfunction "VSS_1_23") (pintype "unspecified"))
      (node (ref "U5") (pin "35") (pinfunction "VSS_2_35") (pintype "unspecified"))
      (node (ref "U5") (pin "47") (pinfunction "VSS_3_47") (pintype "unspecified"))
      (node (ref "U5") (pin "8") (pinfunction "VSSA_8") (pintype "unspecified"))
      (node (ref "USB_TTL1") (pin "4") (pinfunction "GND_4") (pintype "unspecified"))
      (node (ref "USB_TTL1") (pin "5") (pinfunction "GND_5") (pintype "unspecified"))
      (node (ref "USB_TTL1") (pin "6") (pinfunction "GND_6") (pintype "unspecified"))
    )
    (net (code "49") (name "SPINDLE_PWM") (class "Default")
      (node (ref "H6") (pin "1") (pinfunction "1_1") (pintype "input"))
      (node (ref "U5") (pin "29") (pinfunction "PA8_29") (pintype "bidirectional"))
    )
    (net (code "50") (name "SWCLK") (class "Default")
      (node (ref "P5") (pin "3") (pinfunction "3_3") (pintype "input"))
      (node (ref "U5") (pin "37") (pinfunction "PA14/JTCK/SWCLK_37") (pintype "bidirectional"))
    )
    (net (code "51") (name "SWDIO") (class "Default")
      (node (ref "P5") (pin "4") (pinfunction "4_4") (pintype "input"))
      (node (ref "U5") (pin "34") (pinfunction "PA13/JTMS/SWDIO_34") (pintype "bidirectional"))
    )
    (net (code "52") (name "TXD") (class "Default")
      (node (ref "R3") (pin "2") (pinfunction "2_2") (pintype "unspecified"))
      (node (ref "U5") (pin "30") (pinfunction "PA9_30") (pintype "bidirectional"))
    )
    (net (code "53") (name "TXD1") (class "Default")
      (node (ref "P1") (pin "2") (pinfunction "2_2") (pintype "unspecified"))
      (node (ref "R3") (pin "1") (pinfunction "1_1") (pintype "unspecified"))
      (node (ref "U2") (pin "3") (pinfunction "RXD_3") (pintype "unspecified"))
    )
    (net (code "54") (name "TXD3") (class "Default")
      (node (ref "P4") (pin "3") (pinfunction "3_3") (pintype "unspecified"))
      (node (ref "U5") (pin "21") (pinfunction "PB10_21") (pintype "bidirectional"))
    )
    (net (code "55") (name "USB_DM") (class "Default")
      (node (ref "U2") (pin "6") (pinfunction "UD-_6") (pintype "unspecified"))
      (node (ref "USB_TTL1") (pin "2") (pinfunction "D-_2") (pintype "unspecified"))
    )
    (net (code "56") (name "USB_DP") (class "Default")
      (node (ref "U2") (pin "5") (pinfunction "UD+_5") (pintype "unspecified"))
      (node (ref "USB_TTL1") (pin "3") (pinfunction "D+_3") (pintype "unspecified"))
    )
    (net (code "57") (name "VIN_24V") (class "Default")
      (node (ref "C3") (pin "1") (pintype "unspecified"))
      (node (ref "C4") (pin "2") (pinfunction "2_2") (pintype "unspecified"))
      (node (ref "D2") (pin "2") (pinfunction "2_2") (pintype "unspecified"))
      (node (ref "R1") (pin "2") (pinfunction "2_2") (pintype "unspecified"))
      (node (ref "U1") (pin "1") (pinfunction "VIN_1") (pintype "unspecified"))
    )
    (net (code "58") (name "VUSB") (class "Default")
      (node (ref "D1") (pin "1") (pinfunction "1_1") (pintype "unspecified"))
      (node (ref "USB_TTL1") (pin "1") (pinfunction "VBUS_1") (pintype "unspecified"))
    )
    (net (code "59") (name "XTAL1") (class "Default")
      (node (ref "C14") (pin "1") (pinfunction "1_1") (pintype "unspecified"))
      (node (ref "U5") (pin "5") (pinfunction "OSC_IN/PD0_5") (pintype "input"))
      (node (ref "Y2") (pin "1") (pinfunction "OSC1_1") (pintype "unspecified"))
    )
    (net (code "60") (name "XTAL2") (class "Default")
      (node (ref "C13") (pin "1") (pinfunction "1_1") (pintype "unspecified"))
      (node (ref "U5") (pin "6") (pinfunction "OSC_OUT/PD1_6") (pintype "output"))
      (node (ref "Y2") (pin "2") (pinfunction "OSC2_2") (pintype "unspecified"))
    )
    (net (code "61") (name "unconnected-(U2-CTS#-Pad9)") (class "Default")
      (node (ref "U2") (pin "9") (pinfunction "CTS#_9") (pintype "unspecified"))
    )
    (net (code "62") (name "unconnected-(U2-DCD#-Pad12)") (class "Default")
      (node (ref "U2") (pin "12") (pinfunction "DCD#_12") (pintype "unspecified"))
    )
    (net (code "63") (name "unconnected-(U2-DSR#-Pad10)") (class "Default")
      (node (ref "U2") (pin "10") (pinfunction "DSR#_10") (pintype "unspecified"))
    )
    (net (code "64") (name "unconnected-(U2-R232-Pad15)") (class "Default")
      (node (ref "U2") (pin "15") (pinfunction "R232_15") (pintype "unspecified"))
    )
    (net (code "65") (name "unconnected-(U2-RI#-Pad11)") (class "Default")
      (node (ref "U2") (pin "11") (pinfunction "RI#_11") (pintype "unspecified"))
    )
    (net (code "66") (name "unconnected-(U2-RTS#-Pad14)") (class "Default")
      (node (ref "U2") (pin "14") (pinfunction "RTS#_14") (pintype "unspecified"))
    )
    (net (code "67") (name "unconnected-(U5-VBAT-Pad1)") (class "Default")
      (node (ref "U5") (pin "1") (pinfunction "VBAT_1") (pintype "unspecified"))
    )
  )
)
